# MCU.net
KiCad netlist of a schematic drawn in Altium Designer
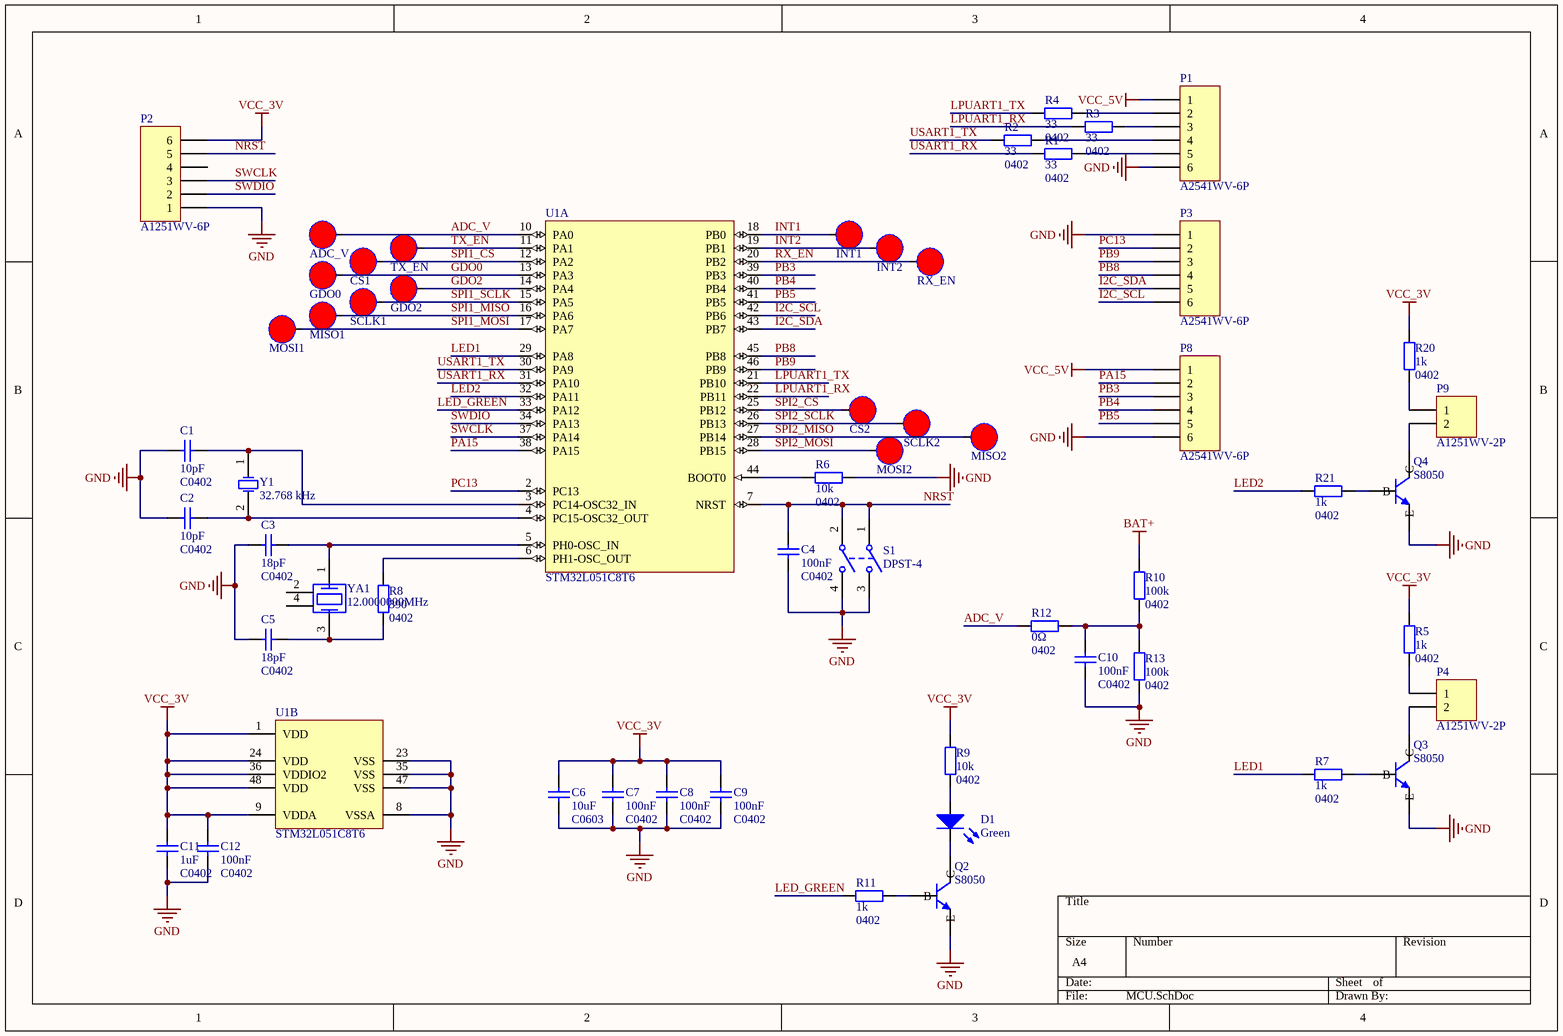
[diagram p0: MCU.SchDoc]

(export (version "E")
  (design (tool "Eeschema 10.0.6"))
  (components
    (comp (ref "ADC_V")
      (value "TP-EMB-SMT-Single-20mil-1pin")
      (footprint "EMB-SMT-40MILX40MIL")
      (description "Test Point Designed for holding a standard probe lead")
      (libsource (lib "RFID_CC1101_433MHz") (part "TP-EMB-SMT-Single-20mil-1pin"))
    )
    (comp (ref "C1")
      (value "10pF")
      (footprint "0402")
      (description "Capacitor (0402,NPO,10pF,DC 50V,±1%) YAGEO")
      (fields (field (name "PACKAGEREFERENCE") "C0402") (field (name "PUBLISHER") "Altium Limited"))
      (libsource (lib "RFID_CC1101_433MHz") (part "CC0402FRNPO9BN100"))
    )
    (comp (ref "C2")
      (value "10pF")
      (footprint "0402")
      (description "Capacitor (0402,NPO,10pF,DC 50V,±1%) YAGEO")
      (fields (field (name "PACKAGEREFERENCE") "C0402") (field (name "PUBLISHER") "Altium Limited"))
      (libsource (lib "RFID_CC1101_433MHz") (part "CC0402FRNPO9BN100"))
    )
    (comp (ref "C3")
      (value "18pF")
      (footprint "0402")
      (description "Capacitor (0402,NPO,18pF,DC 50V,±1%) YAGEO")
      (fields (field (name "PACKAGEREFERENCE") "C0402") (field (name "PUBLISHER") "Altium Limited"))
      (libsource (lib "RFID_CC1101_433MHz") (part "CC0402FRNPO9BN180"))
    )
    (comp (ref "C4")
      (value "100nF")
      (footprint "0402")
      (description "Capacitor (0402,X7R,100nF,DC 50V,±10%) Murata")
      (fields (field (name "PACKAGEREFERENCE") "C0402") (field (name "PUBLISHER") "Altium Limited"))
      (libsource (lib "RFID_CC1101_433MHz") (part "GRM155R71H104KE14"))
    )
    (comp (ref "C5")
      (value "18pF")
      (footprint "0402")
      (description "Capacitor (0402,NPO,18pF,DC 50V,±1%) YAGEO")
      (fields (field (name "PACKAGEREFERENCE") "C0402") (field (name "PUBLISHER") "Altium Limited"))
      (libsource (lib "RFID_CC1101_433MHz") (part "CC0402FRNPO9BN180"))
    )
    (comp (ref "C6")
      (value "10uF")
      (footprint "1608[0603]")
      (description "Capacitor(0603,X5R(EIA),10uF,DC 25V,+/-20 %) muRata")
      (fields (field (name "PACKAGEREFERENCE") "C0603") (field (name "PUBLISHER") "Altium Limited"))
      (libsource (lib "RFID_CC1101_433MHz") (part "GRM188R61E106MA73"))
    )
    (comp (ref "C7")
      (value "100nF")
      (footprint "0402")
      (description "Capacitor (0402,X7R,100nF,DC 50V,±10%) Murata")
      (fields (field (name "PACKAGEREFERENCE") "C0402") (field (name "PUBLISHER") "Altium Limited"))
      (libsource (lib "RFID_CC1101_433MHz") (part "GRM155R71H104KE14"))
    )
    (comp (ref "C8")
      (value "100nF")
      (footprint "0402")
      (description "Capacitor (0402,X7R,100nF,DC 50V,±10%) Murata")
      (fields (field (name "PACKAGEREFERENCE") "C0402") (field (name "PUBLISHER") "Altium Limited"))
      (libsource (lib "RFID_CC1101_433MHz") (part "GRM155R71H104KE14"))
    )
    (comp (ref "C9")
      (value "100nF")
      (footprint "0402")
      (description "Capacitor (0402,X7R,100nF,DC 50V,±10%) Murata")
      (fields (field (name "PACKAGEREFERENCE") "C0402") (field (name "PUBLISHER") "Altium Limited"))
      (libsource (lib "RFID_CC1101_433MHz") (part "GRM155R71H104KE14"))
    )
    (comp (ref "C10")
      (value "100nF")
      (footprint "0402")
      (description "Capacitor (0402,X7R,100nF,DC 50V,±10%) Murata")
      (fields (field (name "PACKAGEREFERENCE") "C0402") (field (name "PUBLISHER") "Altium Limited"))
      (libsource (lib "RFID_CC1101_433MHz") (part "GRM155R71H104KE14"))
    )
    (comp (ref "C11")
      (value "1uF")
      (footprint "0402")
      (description "Capacitor (0402,X5R,1uF,DC 25V,±10%) Murata")
      (fields (field (name "PACKAGEREFERENCE") "C0402") (field (name "PUBLISHER") "Altium Limited"))
      (libsource (lib "RFID_CC1101_433MHz") (part "GRM155R61E105KE11"))
    )
    (comp (ref "C12")
      (value "100nF")
      (footprint "0402")
      (description "Capacitor (0402,X7R,100nF,DC 50V,±10%) Murata")
      (fields (field (name "PACKAGEREFERENCE") "C0402") (field (name "PUBLISHER") "Altium Limited"))
      (libsource (lib "RFID_CC1101_433MHz") (part "GRM155R71H104KE14"))
    )
    (comp (ref "CS1")
      (value "TP-EMB-SMT-Single-20mil-1pin")
      (footprint "EMB-SMT-40MILX40MIL")
      (description "Test Point Designed for holding a standard probe lead")
      (libsource (lib "RFID_CC1101_433MHz") (part "TP-EMB-SMT-Single-20mil-1pin"))
    )
    (comp (ref "CS2")
      (value "TP-EMB-SMT-Single-20mil-1pin")
      (footprint "EMB-SMT-40MILX40MIL")
      (description "Test Point Designed for holding a standard probe lead")
      (libsource (lib "RFID_CC1101_433MHz") (part "TP-EMB-SMT-Single-20mil-1pin"))
    )
    (comp (ref "D1")
      (value "Green")
      (footprint "0603/K")
      (description "Standard 0603 SMD LED, Green, 1.6-2.2V")
      (fields (field (name "PUBLISHER") "Altium Limited"))
      (libsource (lib "RFID_CC1101_433MHz") (part "XL-1608SYGC"))
    )
    (comp (ref "GDO0")
      (value "TP-EMB-SMT-Single-20mil-1pin")
      (footprint "EMB-SMT-40MILX40MIL")
      (description "Test Point Designed for holding a standard probe lead")
      (libsource (lib "RFID_CC1101_433MHz") (part "TP-EMB-SMT-Single-20mil-1pin"))
    )
    (comp (ref "GDO2")
      (value "TP-EMB-SMT-Single-20mil-1pin")
      (footprint "EMB-SMT-40MILX40MIL")
      (description "Test Point Designed for holding a standard probe lead")
      (libsource (lib "RFID_CC1101_433MHz") (part "TP-EMB-SMT-Single-20mil-1pin"))
    )
    (comp (ref "INT1")
      (value "TP-EMB-SMT-Single-20mil-1pin")
      (footprint "EMB-SMT-40MILX40MIL")
      (description "Test Point Designed for holding a standard probe lead")
      (libsource (lib "RFID_CC1101_433MHz") (part "TP-EMB-SMT-Single-20mil-1pin"))
    )
    (comp (ref "INT2")
      (value "TP-EMB-SMT-Single-20mil-1pin")
      (footprint "EMB-SMT-40MILX40MIL")
      (description "Test Point Designed for holding a standard probe lead")
      (libsource (lib "RFID_CC1101_433MHz") (part "TP-EMB-SMT-Single-20mil-1pin"))
    )
    (comp (ref "MISO1")
      (value "TP-EMB-SMT-Single-20mil-1pin")
      (footprint "EMB-SMT-40MILX40MIL")
      (description "Test Point Designed for holding a standard probe lead")
      (libsource (lib "RFID_CC1101_433MHz") (part "TP-EMB-SMT-Single-20mil-1pin"))
    )
    (comp (ref "MISO2")
      (value "TP-EMB-SMT-Single-20mil-1pin")
      (footprint "EMB-SMT-40MILX40MIL")
      (description "Test Point Designed for holding a standard probe lead")
      (libsource (lib "RFID_CC1101_433MHz") (part "TP-EMB-SMT-Single-20mil-1pin"))
    )
    (comp (ref "MOSI1")
      (value "TP-EMB-SMT-Single-20mil-1pin")
      (footprint "EMB-SMT-40MILX40MIL")
      (description "Test Point Designed for holding a standard probe lead")
      (libsource (lib "RFID_CC1101_433MHz") (part "TP-EMB-SMT-Single-20mil-1pin"))
    )
    (comp (ref "MOSI2")
      (value "TP-EMB-SMT-Single-20mil-1pin")
      (footprint "EMB-SMT-40MILX40MIL")
      (description "Test Point Designed for holding a standard probe lead")
      (libsource (lib "RFID_CC1101_433MHz") (part "TP-EMB-SMT-Single-20mil-1pin"))
    )
    (comp (ref "P1")
      (value "A2541WV-6P")
      (footprint "A2541WV-6P")
      (description "Header, 6-Pin, 针座-2.54mm间距，180度，DIP排针")
      (fields (field (name "PUBLISHER") "Altium Limited"))
      (libsource (lib "RFID_CC1101_433MHz") (part "A2541WV-6P"))
    )
    (comp (ref "P2")
      (value "A1251WV-6P")
      (footprint "A1251WV-6P-SWD")
      (description "Header, 6-Pin, 1.25mm PITCH, 180° WAFER")
      (fields (field (name "PUBLISHER") "Altium Limited"))
      (libsource (lib "RFID_CC1101_433MHz") (part "A1251WV-6P"))
    )
    (comp (ref "P3")
      (value "A2541WV-6P")
      (footprint "A2541WV-6P")
      (description "Header, 6-Pin, 针座-2.54mm间距，180度，DIP排针")
      (fields (field (name "PUBLISHER") "Altium Limited"))
      (libsource (lib "RFID_CC1101_433MHz") (part "A2541WV-6P"))
    )
    (comp (ref "P4")
      (value "A1251WV-2P")
      (footprint "A1251WV-2P")
      (description "Header, 2-Pin, 1.25mm PITCH, 180° WAFER")
      (fields (field (name "PUBLISHER") "Altium Limited"))
      (libsource (lib "RFID_CC1101_433MHz") (part "A1251WV-2P"))
    )
    (comp (ref "P8")
      (value "A2541WV-6P")
      (footprint "A2541WV-6P")
      (description "Header, 6-Pin, 针座-2.54mm间距，180度，DIP排针")
      (fields (field (name "PUBLISHER") "Altium Limited"))
      (libsource (lib "RFID_CC1101_433MHz") (part "A2541WV-6P"))
    )
    (comp (ref "P9")
      (value "A1251WV-2P")
      (footprint "A1251WV-2P")
      (description "Header, 2-Pin, 1.25mm PITCH, 180° WAFER")
      (fields (field (name "PUBLISHER") "Altium Limited"))
      (libsource (lib "RFID_CC1101_433MHz") (part "A1251WV-2P"))
    )
    (comp (ref "Q2")
      (value "S8050")
      (footprint "SOT-23B_N")
      (description "NPN General Purpose Amplifier, -55 to +150°C")
      (fields (field (name "MANUFACTURER") "扬州扬杰电子科技股份有限公司"))
      (libsource (lib "RFID_CC1101_433MHz") (part "S8050"))
    )
    (comp (ref "Q3")
      (value "S8050")
      (footprint "SOT-23B_N")
      (description "NPN General Purpose Amplifier, -55 to +150°C")
      (fields (field (name "MANUFACTURER") "扬州扬杰电子科技股份有限公司"))
      (libsource (lib "RFID_CC1101_433MHz") (part "S8050"))
    )
    (comp (ref "Q4")
      (value "S8050")
      (footprint "SOT-23B_N")
      (description "NPN General Purpose Amplifier, -55 to +150°C")
      (fields (field (name "MANUFACTURER") "扬州扬杰电子科技股份有限公司"))
      (libsource (lib "RFID_CC1101_433MHz") (part "S8050"))
    )
    (comp (ref "R1")
      (value "33")
      (footprint "RESC1005X04N")
      (description "Resistor 0402(1005) 33Ω ±1%")
      (fields (field (name "PACKAGEREFERENCE") "0402"))
      (libsource (lib "GPS_NB") (part "RC0402FR-0733RL"))
    )
    (comp (ref "R2")
      (value "33")
      (footprint "RESC1005X04N")
      (description "Resistor 0402(1005) 33Ω ±1%")
      (fields (field (name "PACKAGEREFERENCE") "0402"))
      (libsource (lib "") (part "RC0402FR-0733RL_1"))
    )
    (comp (ref "R3")
      (value "33")
      (footprint "RESC1005X04N")
      (description "Resistor 0402(1005) 33Ω ±1%")
      (fields (field (name "PACKAGEREFERENCE") "0402"))
      (libsource (lib "GPS_NB") (part "RC0402FR-0733RL"))
    )
    (comp (ref "R4")
      (value "33")
      (footprint "RESC1005X04N")
      (description "Resistor 0402(1005) 33Ω ±1%")
      (fields (field (name "PACKAGEREFERENCE") "0402"))
      (libsource (lib "GPS_NB") (part "RC0402FR-0733RL"))
    )
    (comp (ref "R5")
      (value "1k")
      (footprint "RESC1005X04N")
      (description "Resistor 0402(1005) 1kΩ ±1%")
      (fields (field (name "PACKAGEREFERENCE") "0402"))
      (libsource (lib "RFID_CC1101_433MHz") (part "RC0402FR-071KL"))
    )
    (comp (ref "R6")
      (value "10k")
      (footprint "RESC1005X04N")
      (description "Resistor 0402(1005) 10kΩ ±1%")
      (fields (field (name "PACKAGEREFERENCE") "0402"))
      (libsource (lib "RFID_CC1101PA2") (part "RC0402FR-0710KL"))
    )
    (comp (ref "R7")
      (value "1k")
      (footprint "RESC1005X04N")
      (description "Resistor 0402(1005) 1kΩ ±1%")
      (fields (field (name "PACKAGEREFERENCE") "0402"))
      (libsource (lib "GPS_NB") (part "RC0402FR-071KL"))
    )
    (comp (ref "R8")
      (value "390")
      (footprint "RESC1005X04N")
      (description "Resistor 0402(1005) 390Ω ±1%")
      (fields (field (name "PACKAGEREFERENCE") "0402"))
      (libsource (lib "GPS_NB") (part "RC0402FR-07390RL"))
    )
    (comp (ref "R9")
      (value "10k")
      (footprint "RESC1005X04N")
      (description "Resistor 0402(1005) 10kΩ ±1%")
      (fields (field (name "PACKAGEREFERENCE") "0402"))
      (libsource (lib "GPS_NB") (part "RC0402FR-0710KL"))
    )
    (comp (ref "R10")
      (value "100k")
      (footprint "RESC1005X04N")
      (description "Resistor 0402(1005) 100kΩ ±1%")
      (fields (field (name "PACKAGEREFERENCE") "0402"))
      (libsource (lib "GPS_NB") (part "RC0402FR-07100KL"))
    )
    (comp (ref "R11")
      (value "1k")
      (footprint "RESC1005X04N")
      (description "Resistor 0402(1005) 1kΩ ±1%")
      (fields (field (name "PACKAGEREFERENCE") "0402"))
      (libsource (lib "GPS_NB") (part "RC0402FR-071KL"))
    )
    (comp (ref "R12")
      (value "0Ω")
      (footprint "RESC1005X04N")
      (description "Resistor 0402(1005) 0Ω")
      (fields (field (name "PACKAGEREFERENCE") "0402"))
      (libsource (lib "BC26_GNSS") (part "RC0402JR"))
    )
    (comp (ref "R13")
      (value "100k")
      (footprint "RESC1005X04N")
      (description "Resistor 0402(1005) 100kΩ ±1%")
      (fields (field (name "PACKAGEREFERENCE") "0402"))
      (libsource (lib "GPS_NB") (part "RC0402FR-07100KL"))
    )
    (comp (ref "R20")
      (value "1k")
      (footprint "RESC1005X04N")
      (description "Resistor 0402(1005) 1kΩ ±1%")
      (fields (field (name "PACKAGEREFERENCE") "0402"))
      (libsource (lib "RFID_CC1101_433MHz") (part "RC0402FR-071KL"))
    )
    (comp (ref "R21")
      (value "1k")
      (footprint "RESC1005X04N")
      (description "Resistor 0402(1005) 1kΩ ±1%")
      (fields (field (name "PACKAGEREFERENCE") "0402"))
      (libsource (lib "GPS_NB") (part "RC0402FR-071KL"))
    )
    (comp (ref "RX_EN")
      (value "TP-EMB-SMT-Single-20mil-1pin")
      (footprint "EMB-SMT-40MILX40MIL")
      (description "Test Point Designed for holding a standard probe lead")
      (libsource (lib "RFID_CC1101_433MHz") (part "TP-EMB-SMT-Single-20mil-1pin"))
    )
    (comp (ref "S1")
      (value "DPST-4")
      (footprint "DPST")
      (description "5.2*5.2轻触开关")
      (fields (field (name "PUBLISHER") "Altium Limited"))
      (libsource (lib "RFID_CC1101PA2") (part "CX-G001"))
    )
    (comp (ref "SCLK1")
      (value "TP-EMB-SMT-Single-20mil-1pin")
      (footprint "EMB-SMT-40MILX40MIL")
      (description "Test Point Designed for holding a standard probe lead")
      (libsource (lib "RFID_CC1101_433MHz") (part "TP-EMB-SMT-Single-20mil-1pin"))
    )
    (comp (ref "SCLK2")
      (value "TP-EMB-SMT-Single-20mil-1pin")
      (footprint "EMB-SMT-40MILX40MIL")
      (description "Test Point Designed for holding a standard probe lead")
      (libsource (lib "RFID_CC1101_433MHz") (part "TP-EMB-SMT-Single-20mil-1pin"))
    )
    (comp (ref "TX_EN")
      (value "TP-EMB-SMT-Single-20mil-1pin")
      (footprint "EMB-SMT-40MILX40MIL")
      (description "Test Point Designed for holding a standard probe lead")
      (libsource (lib "RFID_CC1101_433MHz") (part "TP-EMB-SMT-Single-20mil-1pin"))
    )
    (comp (ref "U1")
      (value "STM32L051C8T6")
      (footprint "STM-LQFP48_N")
      (libsource (lib "RFID_CC1101_433MHz") (part "STM32L051C8T6"))
    )
    (comp (ref "Y1")
      (value "32.768 kHz")
      (footprint "XTAL-2012")
      (description "Crystal Oscillator, 2.0×1.2×0.6 mm, 2 Pins, 32.768kHz, -40°C~+85°C, 12pF")
      (fields (field (name "MANUFACTURER") "SJK"))
      (libsource (lib "RFID_CC1101_433MHz") (part "7RC32768F12UC"))
    )
    (comp (ref "YA1")
      (value "12.0000000MHz")
      (footprint "XTAL-SMT-4P")
      (description "Crystal Oscillator, 3.2×2.5×0.70 mm, 4 Pins, 12.000MHz, -40°C~+85°C, 12pF, ±10PPM")
      (fields (field (name "MANUFACTURER") "SJK"))
      (libsource (lib "RFID_CC1101_433MHz") (part "7U12000E12UCG"))
    )
  )
  (nets
    (net (code "1") (name "/ADC_V") (class "Default")
      (node (ref "ADC_V") (pin "1") (pinfunction "1_1") (pintype "passive"))
      (node (ref "R12") (pin "1") (pinfunction "1_1") (pintype "passive"))
      (node (ref "U1") (pin "10") (pinfunction "PA0_10") (pintype "bidirectional"))
    )
    (net (code "2") (name "/GDO0") (class "Default")
      (node (ref "GDO0") (pin "1") (pinfunction "1_1") (pintype "passive"))
      (node (ref "U1") (pin "13") (pinfunction "PA3_13") (pintype "bidirectional"))
    )
    (net (code "3") (name "/GDO2") (class "Default")
      (node (ref "GDO2") (pin "1") (pinfunction "1_1") (pintype "passive"))
      (node (ref "U1") (pin "14") (pinfunction "PA4_14") (pintype "bidirectional"))
    )
    (net (code "4") (name "/I2C_SCL") (class "Default")
      (node (ref "P3") (pin "6") (pinfunction "6_6") (pintype "passive"))
      (node (ref "U1") (pin "42") (pinfunction "PB6_42") (pintype "bidirectional"))
    )
    (net (code "5") (name "/I2C_SDA") (class "Default")
      (node (ref "P3") (pin "5") (pinfunction "5_5") (pintype "passive"))
      (node (ref "U1") (pin "43") (pinfunction "PB7_43") (pintype "bidirectional"))
    )
    (net (code "6") (name "/INT1") (class "Default")
      (node (ref "INT1") (pin "1") (pinfunction "1_1") (pintype "passive"))
      (node (ref "U1") (pin "18") (pinfunction "PB0_18") (pintype "bidirectional"))
    )
    (net (code "7") (name "/INT2") (class "Default")
      (node (ref "INT2") (pin "1") (pinfunction "1_1") (pintype "passive"))
      (node (ref "U1") (pin "19") (pinfunction "PB1_19") (pintype "bidirectional"))
    )
    (net (code "8") (name "/LED1") (class "Default")
      (node (ref "R7") (pin "1") (pinfunction "1_1") (pintype "passive"))
      (node (ref "U1") (pin "29") (pinfunction "PA8_29") (pintype "bidirectional"))
    )
    (net (code "9") (name "/LED2") (class "Default")
      (node (ref "R21") (pin "1") (pinfunction "1_1") (pintype "passive"))
      (node (ref "U1") (pin "32") (pinfunction "PA11_32") (pintype "bidirectional"))
    )
    (net (code "10") (name "/LED_GREEN") (class "Default")
      (node (ref "R11") (pin "1") (pinfunction "1_1") (pintype "passive"))
      (node (ref "U1") (pin "33") (pinfunction "PA12_33") (pintype "bidirectional"))
    )
    (net (code "11") (name "/LPUART1_RX") (class "Default")
      (node (ref "R3") (pin "1") (pinfunction "1_1") (pintype "passive"))
      (node (ref "U1") (pin "22") (pinfunction "PB11_22") (pintype "bidirectional"))
    )
    (net (code "12") (name "/LPUART1_TX") (class "Default")
      (node (ref "R4") (pin "1") (pinfunction "1_1") (pintype "passive"))
      (node (ref "U1") (pin "21") (pinfunction "PB10_21") (pintype "bidirectional"))
    )
    (net (code "13") (name "/NRST") (class "Default")
      (node (ref "C4") (pin "2") (pinfunction "2_2") (pintype "passive"))
      (node (ref "P2") (pin "5") (pinfunction "5_5") (pintype "passive"))
      (node (ref "S1") (pin "1") (pinfunction "COMMON1_1") (pintype "passive"))
      (node (ref "S1") (pin "2") (pinfunction "COMMON2_2") (pintype "passive"))
      (node (ref "U1") (pin "7") (pinfunction "NRST_7") (pintype "bidirectional"))
    )
    (net (code "14") (name "/PA15") (class "Default")
      (node (ref "P8") (pin "2") (pinfunction "2_2") (pintype "passive"))
      (node (ref "U1") (pin "38") (pinfunction "PA15_38") (pintype "bidirectional"))
    )
    (net (code "15") (name "/PB3") (class "Default")
      (node (ref "P8") (pin "3") (pinfunction "3_3") (pintype "passive"))
      (node (ref "U1") (pin "39") (pinfunction "PB3_39") (pintype "bidirectional"))
    )
    (net (code "16") (name "/PB4") (class "Default")
      (node (ref "P8") (pin "4") (pinfunction "4_4") (pintype "passive"))
      (node (ref "U1") (pin "40") (pinfunction "PB4_40") (pintype "bidirectional"))
    )
    (net (code "17") (name "/PB5") (class "Default")
      (node (ref "P8") (pin "5") (pinfunction "5_5") (pintype "passive"))
      (node (ref "U1") (pin "41") (pinfunction "PB5_41") (pintype "bidirectional"))
    )
    (net (code "18") (name "/PB8") (class "Default")
      (node (ref "P3") (pin "4") (pinfunction "4_4") (pintype "passive"))
      (node (ref "U1") (pin "45") (pinfunction "PB8_45") (pintype "bidirectional"))
    )
    (net (code "19") (name "/PB9") (class "Default")
      (node (ref "P3") (pin "3") (pinfunction "3_3") (pintype "passive"))
      (node (ref "U1") (pin "46") (pinfunction "PB9_46") (pintype "bidirectional"))
    )
    (net (code "20") (name "/PC13") (class "Default")
      (node (ref "P3") (pin "2") (pinfunction "2_2") (pintype "passive"))
      (node (ref "U1") (pin "2") (pinfunction "PC13_2") (pintype "bidirectional"))
    )
    (net (code "21") (name "/RX_EN") (class "Default")
      (node (ref "RX_EN") (pin "1") (pinfunction "1_1") (pintype "passive"))
      (node (ref "U1") (pin "20") (pinfunction "PB2_20") (pintype "bidirectional"))
    )
    (net (code "22") (name "/SPI1_CS") (class "Default")
      (node (ref "CS1") (pin "1") (pinfunction "1_1") (pintype "passive"))
      (node (ref "U1") (pin "12") (pinfunction "PA2_12") (pintype "bidirectional"))
    )
    (net (code "23") (name "/SPI1_MISO") (class "Default")
      (node (ref "MISO1") (pin "1") (pinfunction "1_1") (pintype "passive"))
      (node (ref "U1") (pin "16") (pinfunction "PA6_16") (pintype "bidirectional"))
    )
    (net (code "24") (name "/SPI1_MOSI") (class "Default")
      (node (ref "MOSI1") (pin "1") (pinfunction "1_1") (pintype "passive"))
      (node (ref "U1") (pin "17") (pinfunction "PA7_17") (pintype "bidirectional"))
    )
    (net (code "25") (name "/SPI1_SCLK") (class "Default")
      (node (ref "SCLK1") (pin "1") (pinfunction "1_1") (pintype "passive"))
      (node (ref "U1") (pin "15") (pinfunction "PA5_15") (pintype "bidirectional"))
    )
    (net (code "26") (name "/SPI2_CS") (class "Default")
      (node (ref "CS2") (pin "1") (pinfunction "1_1") (pintype "passive"))
      (node (ref "U1") (pin "25") (pinfunction "PB12_25") (pintype "bidirectional"))
    )
    (net (code "27") (name "/SPI2_MISO") (class "Default")
      (node (ref "MISO2") (pin "1") (pinfunction "1_1") (pintype "passive"))
      (node (ref "U1") (pin "27") (pinfunction "PB14_27") (pintype "bidirectional"))
    )
    (net (code "28") (name "/SPI2_MOSI") (class "Default")
      (node (ref "MOSI2") (pin "1") (pinfunction "1_1") (pintype "passive"))
      (node (ref "U1") (pin "28") (pinfunction "PB15_28") (pintype "bidirectional"))
    )
    (net (code "29") (name "/SPI2_SCLK") (class "Default")
      (node (ref "SCLK2") (pin "1") (pinfunction "1_1") (pintype "passive"))
      (node (ref "U1") (pin "26") (pinfunction "PB13_26") (pintype "bidirectional"))
    )
    (net (code "30") (name "/SWCLK") (class "Default")
      (node (ref "P2") (pin "3") (pinfunction "3_3") (pintype "passive"))
      (node (ref "U1") (pin "37") (pinfunction "PA14_37") (pintype "bidirectional"))
    )
    (net (code "31") (name "/SWDIO") (class "Default")
      (node (ref "P2") (pin "2") (pinfunction "2_2") (pintype "passive"))
      (node (ref "U1") (pin "34") (pinfunction "PA13_34") (pintype "bidirectional"))
    )
    (net (code "32") (name "/TX_EN") (class "Default")
      (node (ref "TX_EN") (pin "1") (pinfunction "1_1") (pintype "passive"))
      (node (ref "U1") (pin "11") (pinfunction "PA1_11") (pintype "bidirectional"))
    )
    (net (code "33") (name "/USART1_RX") (class "Default")
      (node (ref "R1") (pin "1") (pinfunction "1_1") (pintype "passive"))
      (node (ref "U1") (pin "31") (pinfunction "PA10_31") (pintype "bidirectional"))
    )
    (net (code "34") (name "/USART1_TX") (class "Default")
      (node (ref "R2") (pin "2") (pinfunction "2_2") (pintype "passive"))
      (node (ref "U1") (pin "30") (pinfunction "PA9_30") (pintype "bidirectional"))
    )
    (net (code "35") (name "BAT+") (class "Default")
      (node (ref "R10") (pin "2") (pinfunction "2_2") (pintype "passive"))
    )
    (net (code "36") (name "GND") (class "Default")
      (node (ref "C1") (pin "1") (pinfunction "1_1") (pintype "passive"))
      (node (ref "C10") (pin "1") (pinfunction "1_1") (pintype "passive"))
      (node (ref "C11") (pin "1") (pinfunction "1_1") (pintype "passive"))
      (node (ref "C12") (pin "1") (pinfunction "1_1") (pintype "passive"))
      (node (ref "C2") (pin "1") (pinfunction "1_1") (pintype "passive"))
      (node (ref "C3") (pin "1") (pinfunction "1_1") (pintype "passive"))
      (node (ref "C4") (pin "1") (pinfunction "1_1") (pintype "passive"))
      (node (ref "C5") (pin "1") (pinfunction "1_1") (pintype "passive"))
      (node (ref "C6") (pin "1") (pinfunction "1_1") (pintype "passive"))
      (node (ref "C7") (pin "1") (pinfunction "1_1") (pintype "passive"))
      (node (ref "C8") (pin "1") (pinfunction "1_1") (pintype "passive"))
      (node (ref "C9") (pin "1") (pinfunction "1_1") (pintype "passive"))
      (node (ref "P1") (pin "6") (pinfunction "6_6") (pintype "passive"))
      (node (ref "P2") (pin "1") (pinfunction "1_1") (pintype "passive"))
      (node (ref "P3") (pin "1") (pinfunction "1_1") (pintype "passive"))
      (node (ref "P8") (pin "6") (pinfunction "6_6") (pintype "passive"))
      (node (ref "Q2") (pin "E") (pinfunction "E_E") (pintype "passive"))
      (node (ref "Q3") (pin "E") (pinfunction "E_E") (pintype "passive"))
      (node (ref "Q4") (pin "E") (pinfunction "E_E") (pintype "passive"))
      (node (ref "R13") (pin "1") (pinfunction "1_1") (pintype "passive"))
      (node (ref "R6") (pin "2") (pinfunction "2_2") (pintype "passive"))
      (node (ref "S1") (pin "3") (pinfunction "NO1_3") (pintype "passive"))
      (node (ref "S1") (pin "4") (pinfunction "NO2_4") (pintype "passive"))
      (node (ref "U1") (pin "23") (pinfunction "VSS_23") (pintype "power_in"))
      (node (ref "U1") (pin "35") (pinfunction "VSS_35") (pintype "power_in"))
      (node (ref "U1") (pin "47") (pinfunction "VSS_47") (pintype "power_in"))
      (node (ref "U1") (pin "8") (pinfunction "VSSA_8") (pintype "power_in"))
    )
    (net (code "37") (name "Net-(C5-Pad2)") (class "Default")
      (node (ref "C5") (pin "2") (pinfunction "2_2") (pintype "passive"))
      (node (ref "R8") (pin "1") (pinfunction "1_1") (pintype "passive"))
      (node (ref "YA1") (pin "3") (pinfunction "3_3") (pintype "passive"))
    )
    (net (code "38") (name "Net-(C10-Pad2)") (class "Default")
      (node (ref "C10") (pin "2") (pinfunction "2_2") (pintype "passive"))
      (node (ref "R10") (pin "1") (pinfunction "1_1") (pintype "passive"))
      (node (ref "R12") (pin "2") (pinfunction "2_2") (pintype "passive"))
      (node (ref "R13") (pin "2") (pinfunction "2_2") (pintype "passive"))
    )
    (net (code "39") (name "Net-(D1-PadA)") (class "Default")
      (node (ref "D1") (pin "A") (pinfunction "A_A") (pintype "passive"))
      (node (ref "R9") (pin "1") (pinfunction "1_1") (pintype "passive"))
    )
    (net (code "40") (name "Net-(D1-PadK)") (class "Default")
      (node (ref "D1") (pin "K") (pinfunction "K_K") (pintype "passive"))
      (node (ref "Q2") (pin "C") (pinfunction "C_C") (pintype "passive"))
    )
    (net (code "41") (name "Net-(P1-Pad2)") (class "Default")
      (node (ref "P1") (pin "2") (pinfunction "2_2") (pintype "passive"))
      (node (ref "R4") (pin "2") (pinfunction "2_2") (pintype "passive"))
    )
    (net (code "42") (name "Net-(P1-Pad3)") (class "Default")
      (node (ref "P1") (pin "3") (pinfunction "3_3") (pintype "passive"))
      (node (ref "R3") (pin "2") (pinfunction "2_2") (pintype "passive"))
    )
    (net (code "43") (name "Net-(P1-Pad4)") (class "Default")
      (node (ref "P1") (pin "4") (pinfunction "4_4") (pintype "passive"))
      (node (ref "R2") (pin "1") (pinfunction "1_1") (pintype "passive"))
    )
    (net (code "44") (name "Net-(P1-Pad5)") (class "Default")
      (node (ref "P1") (pin "5") (pinfunction "5_5") (pintype "passive"))
      (node (ref "R1") (pin "2") (pinfunction "2_2") (pintype "passive"))
    )
    (net (code "45") (name "Net-(P4-Pad1)") (class "Default")
      (node (ref "P4") (pin "1") (pinfunction "1_1") (pintype "passive"))
      (node (ref "R5") (pin "1") (pinfunction "1_1") (pintype "passive"))
    )
    (net (code "46") (name "Net-(P4-Pad2)") (class "Default")
      (node (ref "P4") (pin "2") (pinfunction "2_2") (pintype "passive"))
      (node (ref "Q3") (pin "C") (pinfunction "C_C") (pintype "passive"))
    )
    (net (code "47") (name "Net-(P9-Pad1)") (class "Default")
      (node (ref "P9") (pin "1") (pinfunction "1_1") (pintype "passive"))
      (node (ref "R20") (pin "1") (pinfunction "1_1") (pintype "passive"))
    )
    (net (code "48") (name "Net-(P9-Pad2)") (class "Default")
      (node (ref "P9") (pin "2") (pinfunction "2_2") (pintype "passive"))
      (node (ref "Q4") (pin "C") (pinfunction "C_C") (pintype "passive"))
    )
    (net (code "49") (name "Net-(Q2-PadB)") (class "Default")
      (node (ref "Q2") (pin "B") (pinfunction "B_B") (pintype "passive"))
      (node (ref "R11") (pin "2") (pinfunction "2_2") (pintype "passive"))
    )
    (net (code "50") (name "Net-(Q3-PadB)") (class "Default")
      (node (ref "Q3") (pin "B") (pinfunction "B_B") (pintype "passive"))
      (node (ref "R7") (pin "2") (pinfunction "2_2") (pintype "passive"))
    )
    (net (code "51") (name "Net-(Q4-PadB)") (class "Default")
      (node (ref "Q4") (pin "B") (pinfunction "B_B") (pintype "passive"))
      (node (ref "R21") (pin "2") (pinfunction "2_2") (pintype "passive"))
    )
    (net (code "52") (name "Net-(U1A-BOOT0)") (class "Default")
      (node (ref "R6") (pin "1") (pinfunction "1_1") (pintype "passive"))
      (node (ref "U1") (pin "44") (pinfunction "BOOT0_44") (pintype "input"))
    )
    (net (code "53") (name "Net-(U1A-PC14-OSC32_IN)") (class "Default")
      (node (ref "C1") (pin "2") (pinfunction "2_2") (pintype "passive"))
      (node (ref "U1") (pin "3") (pinfunction "PC14-OSC32_IN_3") (pintype "bidirectional"))
      (node (ref "Y1") (pin "1") (pinfunction "OSC1_1") (pintype "passive"))
    )
    (net (code "54") (name "Net-(U1A-PC15-OSC32_OUT)") (class "Default")
      (node (ref "C2") (pin "2") (pinfunction "2_2") (pintype "passive"))
      (node (ref "U1") (pin "4") (pinfunction "PC15-OSC32_OUT_4") (pintype "bidirectional"))
      (node (ref "Y1") (pin "2") (pinfunction "OSC2_2") (pintype "passive"))
    )
    (net (code "55") (name "Net-(U1A-PH0-OSC_IN)") (class "Default")
      (node (ref "C3") (pin "2") (pinfunction "2_2") (pintype "passive"))
      (node (ref "U1") (pin "5") (pinfunction "PH0-OSC_IN_5") (pintype "bidirectional"))
      (node (ref "YA1") (pin "1") (pinfunction "1_1") (pintype "passive"))
    )
    (net (code "56") (name "Net-(U1A-PH1-OSC_OUT)") (class "Default")
      (node (ref "R8") (pin "2") (pinfunction "2_2") (pintype "passive"))
      (node (ref "U1") (pin "6") (pinfunction "PH1-OSC_OUT_6") (pintype "bidirectional"))
    )
    (net (code "57") (name "VCC_3V") (class "Default")
      (node (ref "C11") (pin "2") (pinfunction "2_2") (pintype "passive"))
      (node (ref "C12") (pin "2") (pinfunction "2_2") (pintype "passive"))
      (node (ref "C6") (pin "2") (pinfunction "2_2") (pintype "passive"))
      (node (ref "C7") (pin "2") (pinfunction "2_2") (pintype "passive"))
      (node (ref "C8") (pin "2") (pinfunction "2_2") (pintype "passive"))
      (node (ref "C9") (pin "2") (pinfunction "2_2") (pintype "passive"))
      (node (ref "P2") (pin "6") (pinfunction "6_6") (pintype "passive"))
      (node (ref "R20") (pin "2") (pinfunction "2_2") (pintype "passive"))
      (node (ref "R5") (pin "2") (pinfunction "2_2") (pintype "passive"))
      (node (ref "R9") (pin "2") (pinfunction "2_2") (pintype "passive"))
      (node (ref "U1") (pin "1") (pinfunction "VDD_1") (pintype "power_in"))
      (node (ref "U1") (pin "24") (pinfunction "VDD_24") (pintype "power_in"))
      (node (ref "U1") (pin "36") (pinfunction "VDDIO2_36") (pintype "power_in"))
      (node (ref "U1") (pin "48") (pinfunction "VDD_48") (pintype "power_in"))
      (node (ref "U1") (pin "9") (pinfunction "VDDA_9") (pintype "power_in"))
    )
    (net (code "58") (name "VCC_5V") (class "Default")
      (node (ref "P1") (pin "1") (pinfunction "1_1") (pintype "passive"))
      (node (ref "P8") (pin "1") (pinfunction "1_1") (pintype "passive"))
    )
    (net (code "59") (name "unconnected-(P2-Pad4)") (class "Default")
      (node (ref "P2") (pin "4") (pinfunction "4_4") (pintype "passive"))
    )
    (net (code "60") (name "unconnected-(YA1-Pad2)") (class "Default")
      (node (ref "YA1") (pin "2") (pinfunction "2_2") (pintype "passive"))
    )
    (net (code "61") (name "unconnected-(YA1-Pad4)") (class "Default")
      (node (ref "YA1") (pin "4") (pinfunction "4_4") (pintype "passive"))
    )
  )
)
